# buzzer.net
KiCad netlist of a schematic drawn in Altium Designer
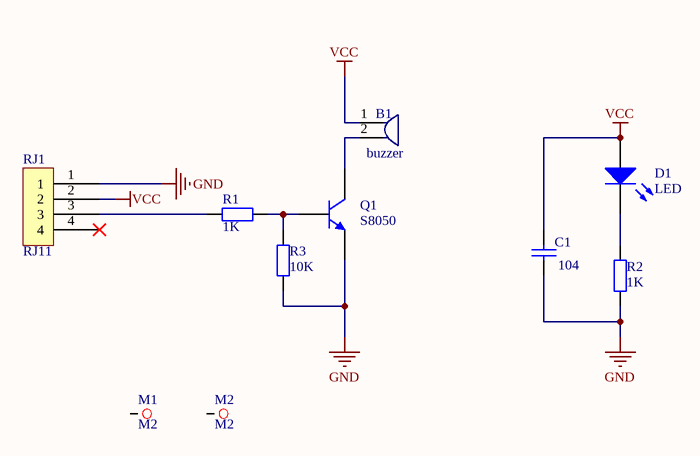
[diagram p0: buzzer.SchDoc]

(export (version "E")
  (design (tool "Eeschema 10.0.6"))
  (components
    (comp (ref "B1") (value "buzzer") (footprint "BUZZER") (libsource (lib "buzzer") (part "buzzer")))
    (comp (ref "C1")
      (value "104")
      (footprint "0603_C")
      (description "Capacitor")
      (fields (field (name "Comment") "Cap") (field (name "PUBLISHER") "Altium Limited"))
      (libsource (lib "Miscellaneous Devices") (part "Cap"))
    )
    (comp (ref "D1")
      (value "LED")
      (footprint "0805")
      (description "Typical RED GaAs LED")
      (fields (field (name "PUBLISHER") "Altium Limited"))
      (libsource (lib "Miscellaneous Devices") (part "LED1"))
    )
    (comp (ref "M1") (value "M2") (footprint "M2") (libsource (lib "QQW-1.SCHLIB") (part "M3")))
    (comp (ref "M2") (value "M2") (footprint "M2") (libsource (lib "QQW-1.SCHLIB") (part "M3")))
    (comp (ref "Q1")
      (value "S8050")
      (footprint "SOT23")
      (description "NPN General Purpose Amplifier")
      (fields (field (name "PUBLISHER") "Altium Limited"))
      (libsource (lib "Miscellaneous Devices") (part "2N3904"))
    )
    (comp (ref "R1")
      (value "1K")
      (footprint "0603_R")
      (description "Resistor")
      (fields (field (name "Comment") "Res2") (field (name "PUBLISHER") "Altium Limited"))
      (libsource (lib "") (part "Res2_2"))
    )
    (comp (ref "R2")
      (value "1K")
      (footprint "0603_R")
      (description "Resistor")
      (fields (field (name "Comment") "Res2") (field (name "PUBLISHER") "Altium Limited"))
      (libsource (lib "") (part "Res2_1"))
    )
    (comp (ref "R3")
      (value "10K")
      (footprint "0603_R")
      (description "Resistor")
      (fields (field (name "Comment") "Res2") (field (name "PUBLISHER") "Altium Limited"))
      (libsource (lib "Miscellaneous Devices") (part "Res2"))
    )
    (comp (ref "RJ1") (value "RJ11") (footprint "RJ11") (libsource (lib "少儿智能车") (part "RJ11")))
  )
  (nets
    (net (code "1") (name "GND") (class "Default")
      (node (ref "C1") (pin "1") (pinfunction "1_1") (pintype "passive"))
      (node (ref "Q1") (pin "1") (pinfunction "E_1") (pintype "passive"))
      (node (ref "R2") (pin "1") (pinfunction "1_1") (pintype "passive"))
      (node (ref "R3") (pin "2") (pinfunction "2_2") (pintype "passive"))
      (node (ref "RJ1") (pin "1") (pinfunction "1_1") (pintype "passive"))
    )
    (net (code "2") (name "Net-(D1-K)") (class "Default")
      (node (ref "D1") (pin "2") (pinfunction "K_2") (pintype "passive"))
      (node (ref "R2") (pin "2") (pinfunction "2_2") (pintype "passive"))
    )
    (net (code "3") (name "Net-(Q1-B)") (class "Default")
      (node (ref "Q1") (pin "2") (pinfunction "B_2") (pintype "passive"))
      (node (ref "R1") (pin "1") (pinfunction "1_1") (pintype "passive"))
      (node (ref "R3") (pin "1") (pinfunction "1_1") (pintype "passive"))
    )
    (net (code "4") (name "Net-(Q1-C)") (class "Default")
      (node (ref "B1") (pin "2") (pinfunction "2_2") (pintype "passive"))
      (node (ref "Q1") (pin "3") (pinfunction "C_3") (pintype "passive"))
    )
    (net (code "5") (name "Net-(R1-Pad2)") (class "Default")
      (node (ref "R1") (pin "2") (pinfunction "2_2") (pintype "passive"))
      (node (ref "RJ1") (pin "3") (pinfunction "3_3") (pintype "passive"))
    )
    (net (code "6") (name "VCC") (class "Default")
      (node (ref "B1") (pin "1") (pinfunction "1_1") (pintype "passive"))
      (node (ref "C1") (pin "2") (pinfunction "2_2") (pintype "passive"))
      (node (ref "D1") (pin "1") (pinfunction "A_1") (pintype "passive"))
      (node (ref "RJ1") (pin "2") (pinfunction "2_2") (pintype "passive"))
    )
    (net (code "7") (name "unconnected-(M1-Pad0)") (class "Default")
      (node (ref "M1") (pin "0") (pinfunction "0_0") (pintype "passive"))
    )
    (net (code "8") (name "unconnected-(M2-Pad0)") (class "Default")
      (node (ref "M2") (pin "0") (pinfunction "0_0") (pintype "passive"))
    )
    (net (code "9") (name "unconnected-(RJ1-Pad4)") (class "Default")
      (node (ref "RJ1") (pin "4") (pinfunction "4_4") (pintype "passive+no_connect"))
    )
  )
)
